# Sender_Board.net
KiCad netlist of a schematic drawn in EAGLE
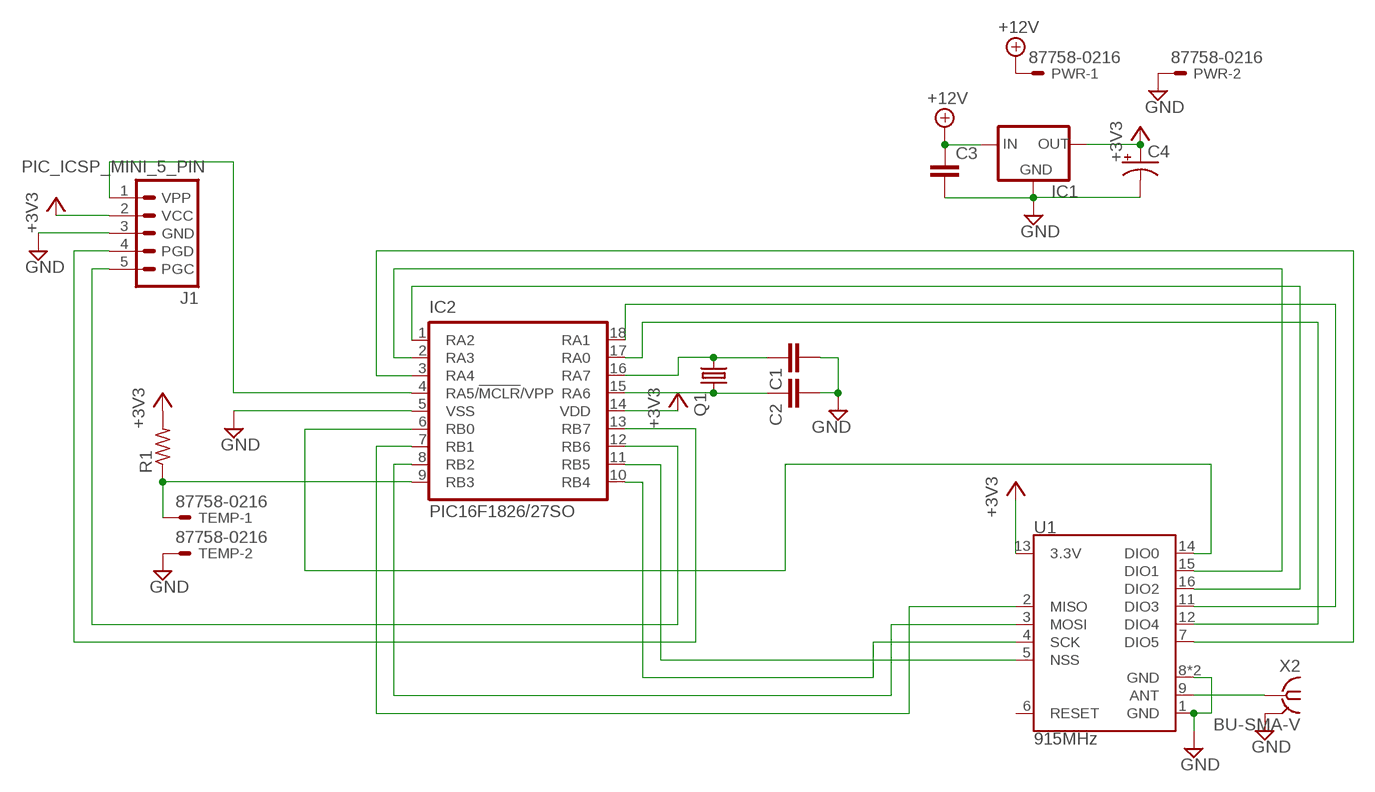
[diagram p0: schematic, sheet 1]

(export (version "E")
  (design (tool "Eeschema 10.0.6"))
  (components
    (comp (ref "C1")
      (value "C-EUC1206")
      (footprint "eagle-import:C1206")
      (libsource (lib "eagle-import") (part "C-EUC1206"))
    )
    (comp (ref "C2")
      (value "C-EUC1206")
      (footprint "eagle-import:C1206")
      (libsource (lib "eagle-import") (part "C-EUC1206"))
    )
    (comp (ref "C3")
      (value "C-EU050-025X075")
      (footprint "eagle-import:C050-025X075")
      (libsource (lib "eagle-import") (part "C-EU050-025X075"))
    )
    (comp (ref "C4")
      (value "CPOL-USE3.5-8")
      (footprint "eagle-import:E3,5-8")
      (libsource (lib "eagle-import") (part "CPOL-USE3.5-8"))
    )
    (comp (ref "IC1")
      (value "78LXX")
      (footprint "eagle-import:78LXX")
      (libsource (lib "eagle-import") (part "78LXX"))
    )
    (comp (ref "IC2")
      (value "PIC16F1826/27SO")
      (footprint "eagle-import:SO-18W")
      (libsource (lib "eagle-import") (part "PIC16F1826/27SO"))
    )
    (comp (ref "J1")
      (value "PIC_ICSP_MINI_5_PIN")
      (footprint "eagle-import:PIC_ICSP_MINI_5_PIN")
      (libsource (lib "eagle-import") (part "PIC_ICSP_MINI_5_PIN"))
    )
    (comp (ref "PWR")
      (value "87758-0216")
      (footprint "eagle-import:87758-0216")
      (libsource (lib "eagle-import") (part "87758-0216"))
    )
    (comp (ref "Q1")
      (value "CRYSTALTC26V")
      (footprint "eagle-import:TC26V")
      (libsource (lib "eagle-import") (part "CRYSTALTC26V"))
    )
    (comp (ref "R1")
      (value "R-US_0204/7")
      (footprint "eagle-import:0204_7")
      (libsource (lib "eagle-import") (part "R-US_0204/7"))
    )
    (comp (ref "TEMP")
      (value "87758-0216")
      (footprint "eagle-import:87758-0216")
      (libsource (lib "eagle-import") (part "87758-0216"))
    )
    (comp (ref "U1")
      (value "915MHz")
      (footprint "eagle-import:RFM69HCW-XXXS2")
      (libsource (lib "eagle-import") (part "RFM69HCW-915"))
    )
    (comp (ref "X2")
      (value "BU-SMA-V")
      (footprint "eagle-import:BU-SMA-V")
      (libsource (lib "eagle-import") (part "BU-SMA-V"))
    )
  )
  (nets
    (net (code "1") (name "+3V3") (class "Default")
      (node (ref "C4") (pin "+") (pinfunction "+_+") (pintype "passive"))
      (node (ref "IC1") (pin "OUT") (pinfunction "OUT_OUT") (pintype "passive"))
      (node (ref "IC2") (pin "14") (pinfunction "VDD_14") (pintype "power_in"))
      (node (ref "J1") (pin "2") (pinfunction "VCC_2") (pintype "passive"))
      (node (ref "R1") (pin "2") (pinfunction "2_2") (pintype "passive"))
      (node (ref "U1") (pin "13") (pinfunction "3.3V_13") (pintype "power_in"))
    )
    (net (code "2") (name "+12V") (class "Default")
      (node (ref "C3") (pin "1") (pinfunction "1_1") (pintype "passive"))
      (node (ref "IC1") (pin "IN") (pinfunction "IN_IN") (pintype "input"))
      (node (ref "PWR") (pin "1") (pinfunction "S_1") (pintype "passive"))
    )
    (net (code "3") (name "GND") (class "Default")
      (node (ref "C1") (pin "2") (pinfunction "2_2") (pintype "passive"))
      (node (ref "C2") (pin "2") (pinfunction "2_2") (pintype "passive"))
      (node (ref "C3") (pin "2") (pinfunction "2_2") (pintype "passive"))
      (node (ref "C4") (pin "-") (pinfunction "-_-") (pintype "passive"))
      (node (ref "IC1") (pin "GND") (pinfunction "GND_GND") (pintype "input"))
      (node (ref "IC2") (pin "5") (pinfunction "VSS_5") (pintype "power_in"))
      (node (ref "J1") (pin "3") (pinfunction "GND_3") (pintype "passive"))
      (node (ref "PWR") (pin "2") (pinfunction "S_2") (pintype "passive"))
      (node (ref "TEMP") (pin "2") (pinfunction "S_2") (pintype "passive"))
      (node (ref "U1") (pin "1") (pinfunction "GND_1") (pintype "power_in"))
      (node (ref "U1") (pin "10") (pinfunction "GND_10") (pintype "power_in"))
      (node (ref "U1") (pin "8") (pinfunction "GND_8") (pintype "power_in"))
      (node (ref "X2") (pin "2") (pinfunction "2_2") (pintype "passive"))
      (node (ref "X2") (pin "3") (pinfunction "2_3") (pintype "passive"))
      (node (ref "X2") (pin "4") (pinfunction "2_4") (pintype "passive"))
      (node (ref "X2") (pin "5") (pinfunction "2_5") (pintype "passive"))
    )
    (net (code "4") (name "Net-(IC2-RA0)") (class "Default")
      (node (ref "IC2") (pin "17") (pinfunction "RA0_17") (pintype "bidirectional"))
      (node (ref "U1") (pin "12") (pinfunction "DIO4_12") (pintype "bidirectional"))
    )
    (net (code "5") (name "Net-(IC2-RA1)") (class "Default")
      (node (ref "IC2") (pin "18") (pinfunction "RA1_18") (pintype "bidirectional"))
      (node (ref "U1") (pin "11") (pinfunction "DIO3_11") (pintype "bidirectional"))
    )
    (net (code "6") (name "Net-(IC2-RA2)") (class "Default")
      (node (ref "IC2") (pin "1") (pinfunction "RA2_1") (pintype "bidirectional"))
      (node (ref "U1") (pin "16") (pinfunction "DIO2_16") (pintype "bidirectional"))
    )
    (net (code "7") (name "Net-(IC2-RA3)") (class "Default")
      (node (ref "IC2") (pin "2") (pinfunction "RA3_2") (pintype "bidirectional"))
      (node (ref "U1") (pin "15") (pinfunction "DIO1_15") (pintype "bidirectional"))
    )
    (net (code "8") (name "Net-(IC2-RA4)") (class "Default")
      (node (ref "IC2") (pin "3") (pinfunction "RA4_3") (pintype "bidirectional"))
      (node (ref "U1") (pin "7") (pinfunction "DIO5_7") (pintype "bidirectional"))
    )
    (net (code "9") (name "Net-(IC2-RA5{slash}~{MCLR}{slash}VPP)") (class "Default")
      (node (ref "IC2") (pin "4") (pinfunction "RA5/~{MCLR}/VPP_4") (pintype "bidirectional"))
      (node (ref "J1") (pin "1") (pinfunction "VPP_1") (pintype "passive"))
    )
    (net (code "10") (name "Net-(IC2-RA6)") (class "Default")
      (node (ref "C2") (pin "1") (pinfunction "1_1") (pintype "passive"))
      (node (ref "IC2") (pin "15") (pinfunction "RA6_15") (pintype "bidirectional"))
      (node (ref "Q1") (pin "2") (pinfunction "2_2") (pintype "passive"))
    )
    (net (code "11") (name "Net-(IC2-RA7)") (class "Default")
      (node (ref "C1") (pin "1") (pinfunction "1_1") (pintype "passive"))
      (node (ref "IC2") (pin "16") (pinfunction "RA7_16") (pintype "bidirectional"))
      (node (ref "Q1") (pin "1") (pinfunction "1_1") (pintype "passive"))
    )
    (net (code "12") (name "Net-(IC2-RB0)") (class "Default")
      (node (ref "IC2") (pin "6") (pinfunction "RB0_6") (pintype "bidirectional"))
      (node (ref "U1") (pin "14") (pinfunction "DIO0_14") (pintype "bidirectional"))
    )
    (net (code "13") (name "Net-(IC2-RB1)") (class "Default")
      (node (ref "IC2") (pin "7") (pinfunction "RB1_7") (pintype "bidirectional"))
      (node (ref "U1") (pin "2") (pinfunction "MISO_2") (pintype "bidirectional"))
    )
    (net (code "14") (name "Net-(IC2-RB2)") (class "Default")
      (node (ref "IC2") (pin "8") (pinfunction "RB2_8") (pintype "bidirectional"))
      (node (ref "U1") (pin "3") (pinfunction "MOSI_3") (pintype "input"))
    )
    (net (code "15") (name "Net-(IC2-RB3)") (class "Default")
      (node (ref "IC2") (pin "9") (pinfunction "RB3_9") (pintype "bidirectional"))
      (node (ref "R1") (pin "1") (pinfunction "1_1") (pintype "passive"))
      (node (ref "TEMP") (pin "1") (pinfunction "S_1") (pintype "passive"))
    )
    (net (code "16") (name "Net-(IC2-RB4)") (class "Default")
      (node (ref "IC2") (pin "10") (pinfunction "RB4_10") (pintype "bidirectional"))
      (node (ref "U1") (pin "4") (pinfunction "SCK_4") (pintype "input"))
    )
    (net (code "17") (name "Net-(IC2-RB5)") (class "Default")
      (node (ref "IC2") (pin "11") (pinfunction "RB5_11") (pintype "bidirectional"))
      (node (ref "U1") (pin "5") (pinfunction "NSS_5") (pintype "input"))
    )
    (net (code "18") (name "Net-(IC2-RB6)") (class "Default")
      (node (ref "IC2") (pin "12") (pinfunction "RB6_12") (pintype "bidirectional"))
      (node (ref "J1") (pin "5") (pinfunction "PGC_5") (pintype "passive"))
    )
    (net (code "19") (name "Net-(IC2-RB7)") (class "Default")
      (node (ref "IC2") (pin "13") (pinfunction "RB7_13") (pintype "bidirectional"))
      (node (ref "J1") (pin "4") (pinfunction "PGD_4") (pintype "passive"))
    )
    (net (code "20") (name "Net-(U1-ANT)") (class "Default")
      (node (ref "U1") (pin "9") (pinfunction "ANT_9") (pintype "passive"))
      (node (ref "X2") (pin "1") (pinfunction "1_1") (pintype "passive"))
    )
    (net (code "21") (name "unconnected-(U1-RESET-Pad6)") (class "Default")
      (node (ref "U1") (pin "6") (pinfunction "RESET_6") (pintype "input"))
    )
  )
)
